# Tesseract.net
KiCad netlist of a schematic drawn in EAGLE
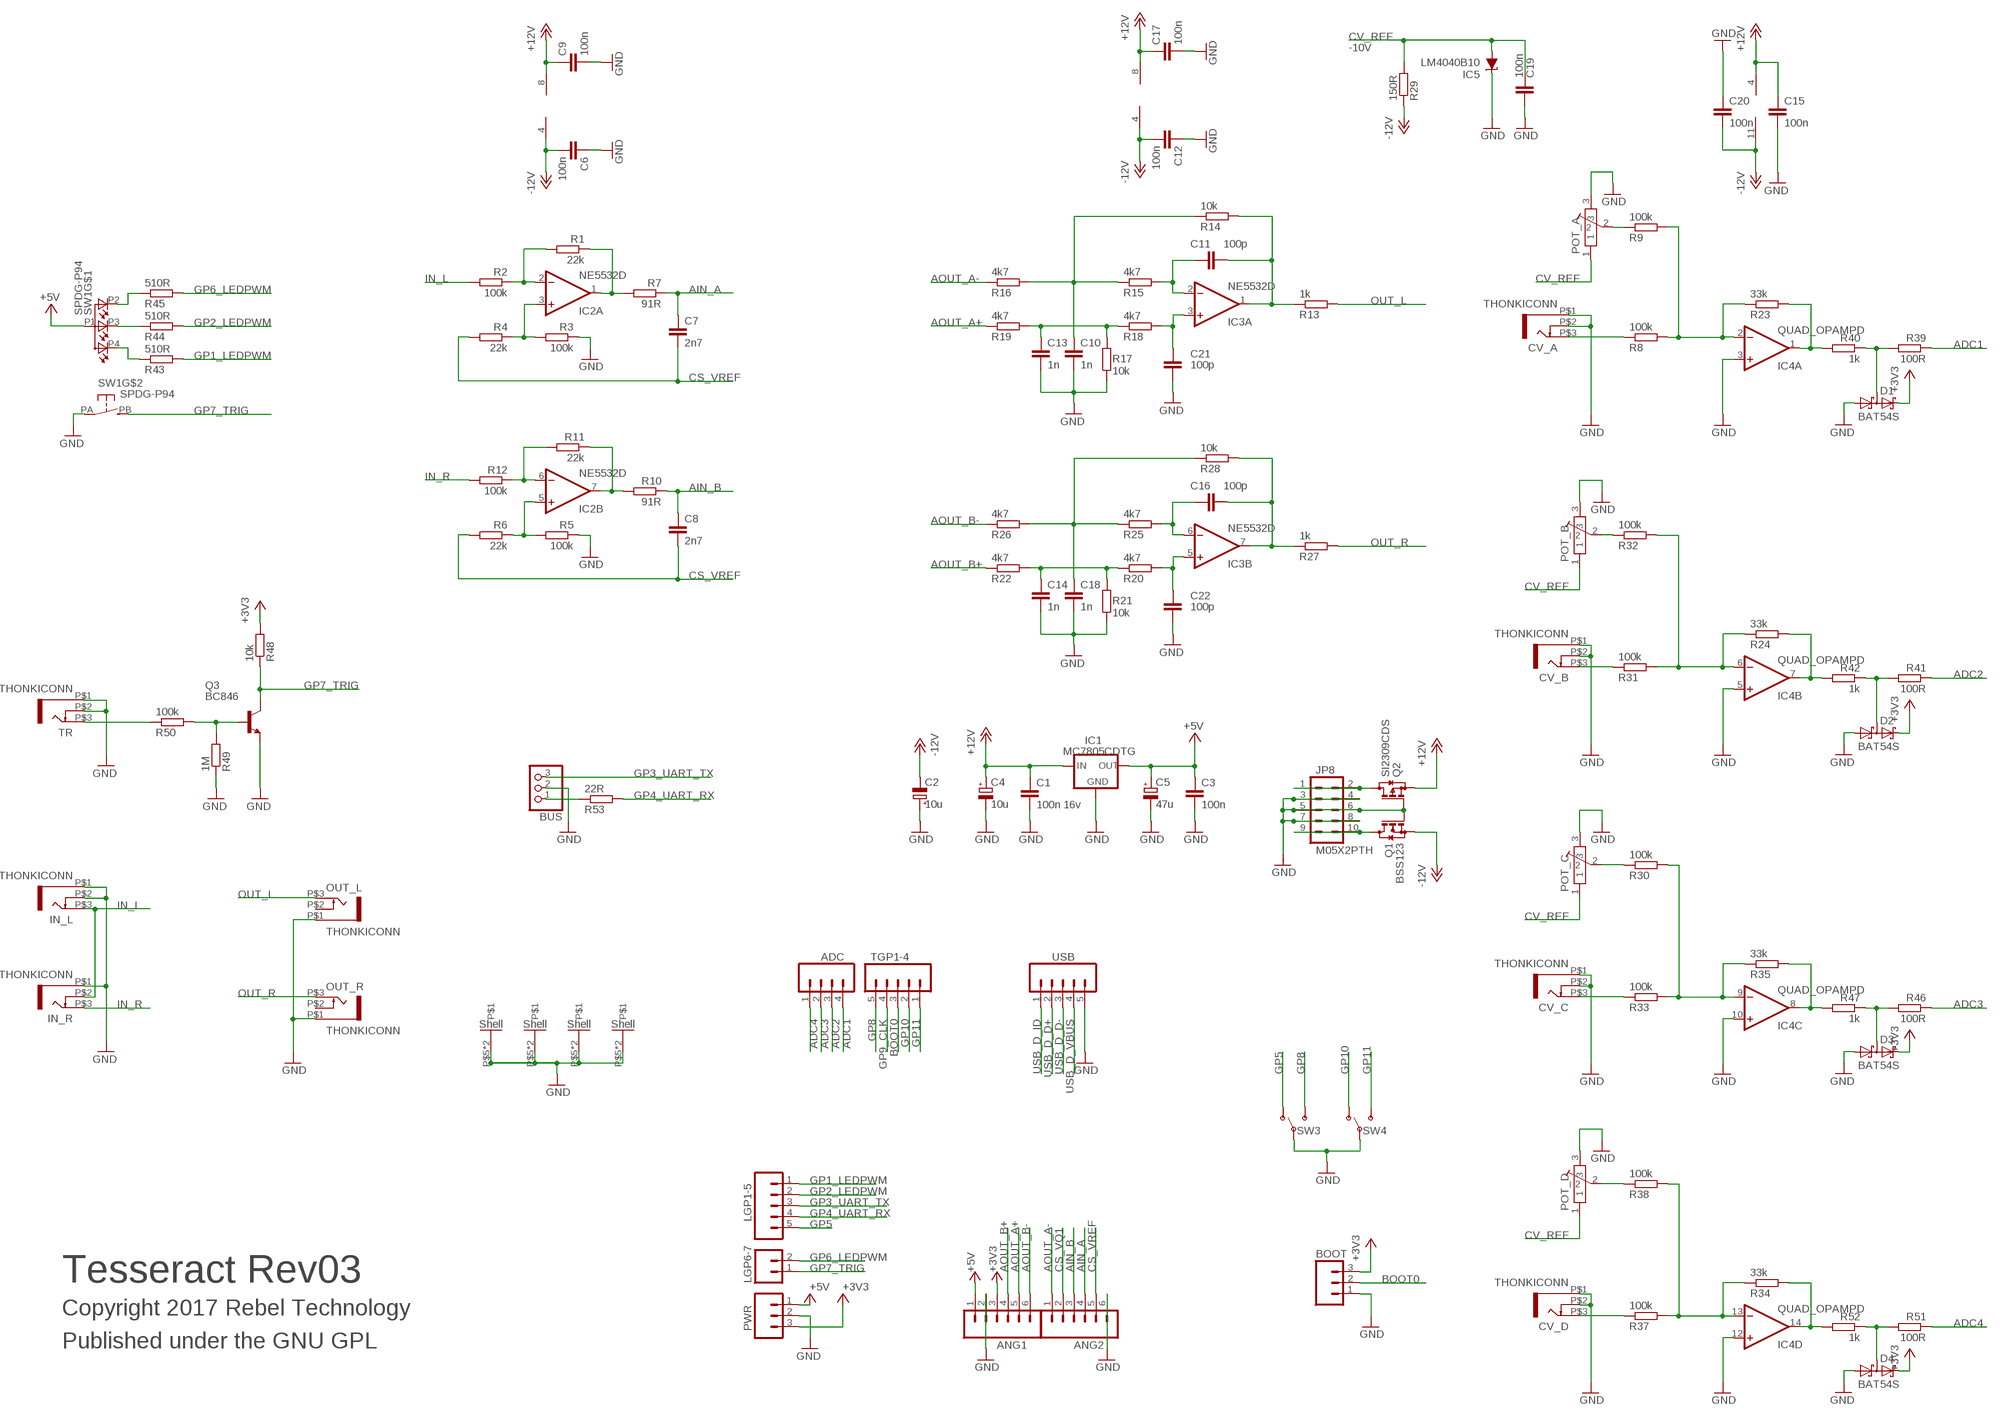
[diagram p0: schematic, sheet 1]

(export (version "E")
  (design (tool "Eeschema 10.0.6"))
  (components
    (comp (ref "ADC")
      (value "M04PTH")
      (footprint "eagle-import:1X04")
      (libsource (lib "eagle-import") (part "M04PTH"))
    )
    (comp (ref "ANG1")
      (value "M06SIP")
      (footprint "eagle-import:1X06")
      (libsource (lib "eagle-import") (part "M06SIP"))
    )
    (comp (ref "ANG2")
      (value "M06SIP")
      (footprint "eagle-import:1X06")
      (libsource (lib "eagle-import") (part "M06SIP"))
    )
    (comp (ref "BOOT")
      (value "M03PTH")
      (footprint "eagle-import:1X03")
      (libsource (lib "eagle-import") (part "M03PTH"))
    )
    (comp (ref "BUS")
      (value "CON-JST-1X03PH-TH")
      (footprint "eagle-import:JST-B3B-PH-KL")
      (libsource (lib "eagle-import") (part "CON-JST-1X03PH-TH"))
    )
    (comp (ref "C1")
      (value "100n 16v")
      (footprint "eagle-import:C0603")
      (libsource (lib "eagle-import") (part "C-EUC0603"))
    )
    (comp (ref "C2")
      (value "10u")
      (footprint "eagle-import:CPOL-5")
      (libsource (lib "eagle-import") (part "CPOL-EU153CLV-0505"))
    )
    (comp (ref "C3")
      (value "100n")
      (footprint "eagle-import:C0603")
      (libsource (lib "eagle-import") (part "C-EUC0603"))
    )
    (comp (ref "C4")
      (value "10u")
      (footprint "eagle-import:CPOL-5")
      (libsource (lib "eagle-import") (part "CPOL-EU153CLV-0505"))
    )
    (comp (ref "C5")
      (value "47u")
      (footprint "eagle-import:PANASONIC_C")
      (libsource (lib "eagle-import") (part "rcl_CPOL-EUC"))
    )
    (comp (ref "C6")
      (value "100n")
      (footprint "eagle-import:C0603")
      (libsource (lib "eagle-import") (part "resistor_C-EUC0603"))
    )
    (comp (ref "C7")
      (value "2n7")
      (footprint "eagle-import:C0603")
      (libsource (lib "eagle-import") (part "resistor_C-EUC0603"))
    )
    (comp (ref "C8")
      (value "2n7")
      (footprint "eagle-import:C0603")
      (libsource (lib "eagle-import") (part "resistor_C-EUC0603"))
    )
    (comp (ref "C9")
      (value "100n")
      (footprint "eagle-import:C0603")
      (libsource (lib "eagle-import") (part "resistor_C-EUC0603"))
    )
    (comp (ref "C10")
      (value "1n")
      (footprint "eagle-import:C0603")
      (libsource (lib "eagle-import") (part "resistor_C-EUC0603"))
    )
    (comp (ref "C11")
      (value "100p")
      (footprint "eagle-import:C0603")
      (libsource (lib "eagle-import") (part "resistor_C-EUC0603"))
    )
    (comp (ref "C12")
      (value "100n")
      (footprint "eagle-import:C0603")
      (libsource (lib "eagle-import") (part "resistor_C-EUC0603"))
    )
    (comp (ref "C13")
      (value "1n")
      (footprint "eagle-import:C0603")
      (libsource (lib "eagle-import") (part "resistor_C-EUC0603"))
    )
    (comp (ref "C14")
      (value "1n")
      (footprint "eagle-import:C0603")
      (libsource (lib "eagle-import") (part "resistor_C-EUC0603"))
    )
    (comp (ref "C15")
      (value "100n")
      (footprint "eagle-import:C0603")
      (libsource (lib "eagle-import") (part "resistor_C-EUC0603"))
    )
    (comp (ref "C16")
      (value "100p")
      (footprint "eagle-import:C0603")
      (libsource (lib "eagle-import") (part "resistor_C-EUC0603"))
    )
    (comp (ref "C17")
      (value "100n")
      (footprint "eagle-import:C0603")
      (libsource (lib "eagle-import") (part "resistor_C-EUC0603"))
    )
    (comp (ref "C18")
      (value "1n")
      (footprint "eagle-import:C0603")
      (libsource (lib "eagle-import") (part "resistor_C-EUC0603"))
    )
    (comp (ref "C19")
      (value "100n")
      (footprint "eagle-import:C0603")
      (libsource (lib "eagle-import") (part "resistor_C-EUC0603"))
    )
    (comp (ref "C20")
      (value "100n")
      (footprint "eagle-import:C0603")
      (libsource (lib "eagle-import") (part "resistor_C-EUC0603"))
    )
    (comp (ref "C21")
      (value "100p")
      (footprint "eagle-import:C0603")
      (libsource (lib "eagle-import") (part "resistor_C-EUC0603"))
    )
    (comp (ref "C22")
      (value "100p")
      (footprint "eagle-import:C0603")
      (libsource (lib "eagle-import") (part "resistor_C-EUC0603"))
    )
    (comp (ref "CV_A")
      (value "THONKICONN")
      (footprint "eagle-import:THONKICONN")
      (libsource (lib "eagle-import") (part "THONKICONN"))
    )
    (comp (ref "CV_B")
      (value "THONKICONN")
      (footprint "eagle-import:THONKICONN")
      (libsource (lib "eagle-import") (part "THONKICONN"))
    )
    (comp (ref "CV_C")
      (value "THONKICONN")
      (footprint "eagle-import:THONKICONN")
      (libsource (lib "eagle-import") (part "THONKICONN"))
    )
    (comp (ref "CV_D")
      (value "THONKICONN")
      (footprint "eagle-import:THONKICONN")
      (libsource (lib "eagle-import") (part "THONKICONN"))
    )
    (comp (ref "D1")
      (value "BAT54S")
      (footprint "eagle-import:SOT23")
      (libsource (lib "eagle-import") (part "BAT54S"))
    )
    (comp (ref "D2")
      (value "BAT54S")
      (footprint "eagle-import:SOT23")
      (libsource (lib "eagle-import") (part "BAT54S"))
    )
    (comp (ref "D3")
      (value "BAT54S")
      (footprint "eagle-import:SOT23")
      (libsource (lib "eagle-import") (part "BAT54S"))
    )
    (comp (ref "D4")
      (value "BAT54S")
      (footprint "eagle-import:SOT23")
      (libsource (lib "eagle-import") (part "BAT54S"))
    )
    (comp (ref "IC1")
      (value "MC7805CDTG")
      (footprint "eagle-import:DPACK")
      (libsource (lib "eagle-import") (part "MC78XX"))
    )
    (comp (ref "IC2")
      (value "NE5532D")
      (footprint "eagle-import:SO08")
      (libsource (lib "eagle-import") (part "NE5532D"))
    )
    (comp (ref "IC3")
      (value "NE5532D")
      (footprint "eagle-import:SO08")
      (libsource (lib "eagle-import") (part "NE5532D"))
    )
    (comp (ref "IC4")
      (value "QUAD_OPAMPD")
      (footprint "eagle-import:SO14")
      (libsource (lib "eagle-import") (part "QUAD_OPAMPD"))
    )
    (comp (ref "IC5")
      (value "LM4040B10")
      (footprint "eagle-import:DBZ_R-PDSO-G3")
      (fields (field (name "MF") "TEXAS INSTRUMENT CONNECTORS") (field (name "MPN") "LM4041C12QDBZT"))
      (libsource (lib "eagle-import") (part "LM4041DBZC12"))
    )
    (comp (ref "IN_L")
      (value "THONKICONN")
      (footprint "eagle-import:THONKICONN")
      (libsource (lib "eagle-import") (part "THONKICONN"))
    )
    (comp (ref "IN_R")
      (value "THONKICONN")
      (footprint "eagle-import:THONKICONN")
      (libsource (lib "eagle-import") (part "THONKICONN"))
    )
    (comp (ref "JP8")
      (value "M05X2PTH")
      (footprint "eagle-import:AVR_ICSP")
      (libsource (lib "eagle-import") (part "M05X2PTH"))
    )
    (comp (ref "LGP1-5")
      (value "M05PTH")
      (footprint "eagle-import:1X05")
      (libsource (lib "eagle-import") (part "M05PTH"))
    )
    (comp (ref "LGP6-7")
      (value "M02PTH")
      (footprint "eagle-import:1X02")
      (libsource (lib "eagle-import") (part "M02PTH"))
    )
    (comp (ref "OUT_L")
      (value "THONKICONN")
      (footprint "eagle-import:THONKICONN")
      (libsource (lib "eagle-import") (part "THONKICONN"))
    )
    (comp (ref "OUT_R")
      (value "THONKICONN")
      (footprint "eagle-import:THONKICONN")
      (libsource (lib "eagle-import") (part "THONKICONN"))
    )
    (comp (ref "POT_A")
      (value "POT-ALPS-RK09L1140")
      (footprint "eagle-import:POT-ALPS-RK09L1140")
      (libsource (lib "eagle-import") (part "POT-ALPS-RK09L1140"))
    )
    (comp (ref "POT_B")
      (value "POT-ALPS-RK09L1140")
      (footprint "eagle-import:POT-ALPS-RK09L1140")
      (libsource (lib "eagle-import") (part "POT-ALPS-RK09L1140"))
    )
    (comp (ref "POT_C")
      (value "POT-ALPS-RK09L1140")
      (footprint "eagle-import:POT-ALPS-RK09L1140")
      (libsource (lib "eagle-import") (part "POT-ALPS-RK09L1140"))
    )
    (comp (ref "POT_D")
      (value "POT-ALPS-RK09L1140")
      (footprint "eagle-import:POT-ALPS-RK09L1140")
      (libsource (lib "eagle-import") (part "POT-ALPS-RK09L1140"))
    )
    (comp (ref "PWR")
      (value "M03PTH")
      (footprint "eagle-import:1X03")
      (libsource (lib "eagle-import") (part "M03PTH"))
    )
    (comp (ref "Q1")
      (value "BSS123")
      (footprint "eagle-import:SOT23")
      (libsource (lib "eagle-import") (part "BSS123"))
    )
    (comp (ref "Q2")
      (value "SI2309CDS")
      (footprint "eagle-import:SOT23")
      (libsource (lib "eagle-import") (part "BSS84"))
    )
    (comp (ref "Q3")
      (value "BC846")
      (footprint "eagle-import:SOT23")
      (libsource (lib "eagle-import") (part "BC846"))
    )
    (comp (ref "R1")
      (value "22k")
      (footprint "eagle-import:0603")
      (libsource (lib "eagle-import") (part "R-EU_0603"))
    )
    (comp (ref "R2")
      (value "100k")
      (footprint "eagle-import:0603")
      (libsource (lib "eagle-import") (part "R-EU_0603"))
    )
    (comp (ref "R3")
      (value "100k")
      (footprint "eagle-import:0603")
      (libsource (lib "eagle-import") (part "R-EU_0603"))
    )
    (comp (ref "R4")
      (value "22k")
      (footprint "eagle-import:0603")
      (libsource (lib "eagle-import") (part "R-EU_0603"))
    )
    (comp (ref "R5")
      (value "100k")
      (footprint "eagle-import:0603")
      (libsource (lib "eagle-import") (part "R-EU_0603"))
    )
    (comp (ref "R6")
      (value "22k")
      (footprint "eagle-import:0603")
      (libsource (lib "eagle-import") (part "R-EU_0603"))
    )
    (comp (ref "R7")
      (value "91R")
      (footprint "eagle-import:0603")
      (libsource (lib "eagle-import") (part "R-EU_0603"))
    )
    (comp (ref "R8")
      (value "100k")
      (footprint "eagle-import:0603")
      (libsource (lib "eagle-import") (part "R-EU_0603"))
    )
    (comp (ref "R9")
      (value "100k")
      (footprint "eagle-import:0603")
      (libsource (lib "eagle-import") (part "R-EU_0603"))
    )
    (comp (ref "R10")
      (value "91R")
      (footprint "eagle-import:0603")
      (libsource (lib "eagle-import") (part "R-EU_0603"))
    )
    (comp (ref "R11")
      (value "22k")
      (footprint "eagle-import:0603")
      (libsource (lib "eagle-import") (part "R-EU_0603"))
    )
    (comp (ref "R12")
      (value "100k")
      (footprint "eagle-import:0603")
      (libsource (lib "eagle-import") (part "R-EU_0603"))
    )
    (comp (ref "R13")
      (value "1k")
      (footprint "eagle-import:0603")
      (libsource (lib "eagle-import") (part "R-EU_0603"))
    )
    (comp (ref "R14")
      (value "10k")
      (footprint "eagle-import:0603")
      (libsource (lib "eagle-import") (part "R-EU_0603"))
    )
    (comp (ref "R15")
      (value "4k7")
      (footprint "eagle-import:0603")
      (libsource (lib "eagle-import") (part "R-EU_0603"))
    )
    (comp (ref "R16")
      (value "4k7")
      (footprint "eagle-import:0603")
      (libsource (lib "eagle-import") (part "R-EU_0603"))
    )
    (comp (ref "R17")
      (value "10k")
      (footprint "eagle-import:0603")
      (libsource (lib "eagle-import") (part "R-EU_0603"))
    )
    (comp (ref "R18")
      (value "4k7")
      (footprint "eagle-import:0603")
      (libsource (lib "eagle-import") (part "R-EU_0603"))
    )
    (comp (ref "R19")
      (value "4k7")
      (footprint "eagle-import:0603")
      (libsource (lib "eagle-import") (part "R-EU_0603"))
    )
    (comp (ref "R20")
      (value "4k7")
      (footprint "eagle-import:0603")
      (libsource (lib "eagle-import") (part "R-EU_0603"))
    )
    (comp (ref "R21")
      (value "10k")
      (footprint "eagle-import:0603")
      (libsource (lib "eagle-import") (part "R-EU_0603"))
    )
    (comp (ref "R22")
      (value "4k7")
      (footprint "eagle-import:0603")
      (libsource (lib "eagle-import") (part "R-EU_0603"))
    )
    (comp (ref "R23")
      (value "33k")
      (footprint "eagle-import:0603")
      (libsource (lib "eagle-import") (part "R-EU_0603"))
    )
    (comp (ref "R24")
      (value "33k")
      (footprint "eagle-import:0603")
      (libsource (lib "eagle-import") (part "R-EU_0603"))
    )
    (comp (ref "R25")
      (value "4k7")
      (footprint "eagle-import:0603")
      (libsource (lib "eagle-import") (part "R-EU_0603"))
    )
    (comp (ref "R26")
      (value "4k7")
      (footprint "eagle-import:0603")
      (libsource (lib "eagle-import") (part "R-EU_0603"))
    )
    (comp (ref "R27")
      (value "1k")
      (footprint "eagle-import:0603")
      (libsource (lib "eagle-import") (part "R-EU_0603"))
    )
    (comp (ref "R28")
      (value "10k")
      (footprint "eagle-import:0603")
      (libsource (lib "eagle-import") (part "R-EU_0603"))
    )
    (comp (ref "R29")
      (value "150R")
      (footprint "eagle-import:0603")
      (libsource (lib "eagle-import") (part "R-EU_0603"))
    )
    (comp (ref "R30")
      (value "100k")
      (footprint "eagle-import:0603")
      (libsource (lib "eagle-import") (part "R-EU_0603"))
    )
    (comp (ref "R31")
      (value "100k")
      (footprint "eagle-import:0603")
      (libsource (lib "eagle-import") (part "R-EU_0603"))
    )
    (comp (ref "R32")
      (value "100k")
      (footprint "eagle-import:0603")
      (libsource (lib "eagle-import") (part "R-EU_0603"))
    )
    (comp (ref "R33")
      (value "100k")
      (footprint "eagle-import:0603")
      (libsource (lib "eagle-import") (part "R-EU_0603"))
    )
    (comp (ref "R34")
      (value "33k")
      (footprint "eagle-import:0603")
      (libsource (lib "eagle-import") (part "R-EU_0603"))
    )
    (comp (ref "R35")
      (value "33k")
      (footprint "eagle-import:0603")
      (libsource (lib "eagle-import") (part "R-EU_0603"))
    )
    (comp (ref "R37")
      (value "100k")
      (footprint "eagle-import:0603")
      (libsource (lib "eagle-import") (part "R-EU_0603"))
    )
    (comp (ref "R38")
      (value "100k")
      (footprint "eagle-import:0603")
      (libsource (lib "eagle-import") (part "R-EU_0603"))
    )
    (comp (ref "R39")
      (value "100R")
      (footprint "eagle-import:0603")
      (libsource (lib "eagle-import") (part "R-EU_0603"))
    )
    (comp (ref "R40")
      (value "1k")
      (footprint "eagle-import:0603")
      (libsource (lib "eagle-import") (part "R-EU_0603"))
    )
    (comp (ref "R41")
      (value "100R")
      (footprint "eagle-import:0603")
      (libsource (lib "eagle-import") (part "R-EU_0603"))
    )
    (comp (ref "R42")
      (value "1k")
      (footprint "eagle-import:0603")
      (libsource (lib "eagle-import") (part "R-EU_0603"))
    )
    (comp (ref "R43")
      (value "510R")
      (footprint "eagle-import:0603")
      (libsource (lib "eagle-import") (part "R-EU_0603"))
    )
    (comp (ref "R44")
      (value "510R")
      (footprint "eagle-import:0603")
      (libsource (lib "eagle-import") (part "R-EU_0603"))
    )
    (comp (ref "R45")
      (value "510R")
      (footprint "eagle-import:0603")
      (libsource (lib "eagle-import") (part "R-EU_0603"))
    )
    (comp (ref "R46")
      (value "100R")
      (footprint "eagle-import:0603")
      (libsource (lib "eagle-import") (part "R-EU_0603"))
    )
    (comp (ref "R47")
      (value "1k")
      (footprint "eagle-import:0603")
      (libsource (lib "eagle-import") (part "R-EU_0603"))
    )
    (comp (ref "R48")
      (value "10k")
      (footprint "eagle-import:0603")
      (libsource (lib "eagle-import") (part "R-EU_0603"))
    )
    (comp (ref "R49")
      (value "1M")
      (footprint "eagle-import:0603")
      (libsource (lib "eagle-import") (part "R-EU_0603"))
    )
    (comp (ref "R50")
      (value "100k")
      (footprint "eagle-import:0603")
      (libsource (lib "eagle-import") (part "R-EU_0603"))
    )
    (comp (ref "R51")
      (value "100R")
      (footprint "eagle-import:0603")
      (libsource (lib "eagle-import") (part "R-EU_0603"))
    )
    (comp (ref "R52")
      (value "1k")
      (footprint "eagle-import:0603")
      (libsource (lib "eagle-import") (part "R-EU_0603"))
    )
    (comp (ref "R53")
      (value "22R")
      (footprint "eagle-import:0603")
      (libsource (lib "eagle-import") (part "R-EU_0603"))
    )
    (comp (ref "SW1")
      (value "SPDG-P94")
      (footprint "eagle-import:SPDG-P94")
      (libsource (lib "eagle-import") (part "SPDG-P94"))
    )
    (comp (ref "SW3")
      (value "SUB-MIN-SPDT")
      (footprint "eagle-import:SUB-MIN-SPDT")
      (libsource (lib "eagle-import") (part "SUB-MIN-SPDT"))
    )
    (comp (ref "SW4")
      (value "SUB-MIN-SPDT")
      (footprint "eagle-import:SUB-MIN-SPDT")
      (libsource (lib "eagle-import") (part "SUB-MIN-SPDT"))
    )
    (comp (ref "TGP1-4")
      (value "M05PTH")
      (footprint "eagle-import:1X05")
      (libsource (lib "eagle-import") (part "M05PTH"))
    )
    (comp (ref "TR")
      (value "THONKICONN")
      (footprint "eagle-import:THONKICONN")
      (libsource (lib "eagle-import") (part "THONKICONN"))
    )
    (comp (ref "USB")
      (value "M05PTH")
      (footprint "eagle-import:1X05")
      (libsource (lib "eagle-import") (part "M05PTH"))
    )
  )
  (nets
    (net (code "1") (name "+3V3") (class "Default")
      (node (ref "ANG1") (pin "3") (pinfunction "3_3") (pintype "passive"))
      (node (ref "BOOT") (pin "3") (pinfunction "3_3") (pintype "passive"))
      (node (ref "D1") (pin "2") (pinfunction "C2_2") (pintype "passive"))
      (node (ref "D2") (pin "2") (pinfunction "C2_2") (pintype "passive"))
      (node (ref "D3") (pin "2") (pinfunction "C2_2") (pintype "passive"))
      (node (ref "D4") (pin "2") (pinfunction "C2_2") (pintype "passive"))
      (node (ref "PWR") (pin "3") (pinfunction "3_3") (pintype "passive"))
      (node (ref "R48") (pin "2") (pinfunction "2_2") (pintype "passive"))
    )
    (net (code "2") (name "+5V") (class "Default")
      (node (ref "ANG1") (pin "1") (pinfunction "1_1") (pintype "passive"))
      (node (ref "C3") (pin "1") (pinfunction "1_1") (pintype "passive"))
      (node (ref "C5") (pin "+") (pinfunction "+_+") (pintype "passive"))
      (node (ref "IC1") (pin "3") (pinfunction "OUT_3") (pintype "passive"))
      (node (ref "PWR") (pin "1") (pinfunction "1_1") (pintype "passive"))
      (node (ref "SW1") (pin "P1") (pinfunction "A_P1") (pintype "passive"))
    )
    (net (code "3") (name "+12V") (class "Default")
      (node (ref "C1") (pin "1") (pinfunction "1_1") (pintype "passive"))
      (node (ref "C15") (pin "1") (pinfunction "1_1") (pintype "passive"))
      (node (ref "C17") (pin "1") (pinfunction "1_1") (pintype "passive"))
      (node (ref "C4") (pin "+") (pinfunction "+_+") (pintype "passive"))
      (node (ref "C9") (pin "1") (pinfunction "1_1") (pintype "passive"))
      (node (ref "IC1") (pin "1") (pinfunction "IN_1") (pintype "input"))
      (node (ref "IC2") (pin "8") (pinfunction "V+_8") (pintype "power_in"))
      (node (ref "IC3") (pin "8") (pinfunction "V+_8") (pintype "power_in"))
      (node (ref "IC4") (pin "4") (pinfunction "V+_4") (pintype "power_in"))
      (node (ref "Q2") (pin "2") (pinfunction "S_2") (pintype "passive"))
    )
    (net (code "4") (name "-12V") (class "Default")
      (node (ref "C12") (pin "2") (pinfunction "2_2") (pintype "passive"))
      (node (ref "C2") (pin "-") (pinfunction "-_-") (pintype "passive"))
      (node (ref "C20") (pin "2") (pinfunction "2_2") (pintype "passive"))
      (node (ref "C6") (pin "2") (pinfunction "2_2") (pintype "passive"))
      (node (ref "IC2") (pin "4") (pinfunction "V-_4") (pintype "power_in"))
      (node (ref "IC3") (pin "4") (pinfunction "V-_4") (pintype "power_in"))
      (node (ref "IC4") (pin "11") (pinfunction "V-_11") (pintype "power_in"))
      (node (ref "Q1") (pin "2") (pinfunction "S_2") (pintype "passive"))
      (node (ref "R29") (pin "1") (pinfunction "1_1") (pintype "passive"))
    )
    (net (code "5") (name "/ADC1") (class "Default")
      (node (ref "ADC") (pin "4") (pinfunction "4_4") (pintype "passive"))
      (node (ref "R39") (pin "1") (pinfunction "1_1") (pintype "passive"))
    )
    (net (code "6") (name "/ADC2") (class "Default")
      (node (ref "ADC") (pin "3") (pinfunction "3_3") (pintype "passive"))
      (node (ref "R41") (pin "1") (pinfunction "1_1") (pintype "passive"))
    )
    (net (code "7") (name "/ADC3") (class "Default")
      (node (ref "ADC") (pin "2") (pinfunction "2_2") (pintype "passive"))
      (node (ref "R46") (pin "1") (pinfunction "1_1") (pintype "passive"))
    )
    (net (code "8") (name "/ADC4") (class "Default")
      (node (ref "ADC") (pin "1") (pinfunction "1_1") (pintype "passive"))
      (node (ref "R51") (pin "1") (pinfunction "1_1") (pintype "passive"))
    )
    (net (code "9") (name "/AIN_A") (class "Default")
      (node (ref "ANG2") (pin "4") (pinfunction "4_4") (pintype "passive"))
      (node (ref "C7") (pin "1") (pinfunction "1_1") (pintype "passive"))
      (node (ref "R7") (pin "1") (pinfunction "1_1") (pintype "passive"))
    )
    (net (code "10") (name "/AIN_B") (class "Default")
      (node (ref "ANG2") (pin "3") (pinfunction "3_3") (pintype "passive"))
      (node (ref "C8") (pin "1") (pinfunction "1_1") (pintype "passive"))
      (node (ref "R10") (pin "1") (pinfunction "1_1") (pintype "passive"))
    )
    (net (code "11") (name "/AOUT_A+") (class "Default")
      (node (ref "ANG1") (pin "5") (pinfunction "5_5") (pintype "passive"))
      (node (ref "R19") (pin "1") (pinfunction "1_1") (pintype "passive"))
    )
    (net (code "12") (name "/AOUT_A-") (class "Default")
      (node (ref "ANG2") (pin "1") (pinfunction "1_1") (pintype "passive"))
      (node (ref "R16") (pin "1") (pinfunction "1_1") (pintype "passive"))
    )
    (net (code "13") (name "/AOUT_B+") (class "Default")
      (node (ref "ANG1") (pin "4") (pinfunction "4_4") (pintype "passive"))
      (node (ref "R22") (pin "1") (pinfunction "1_1") (pintype "passive"))
    )
    (net (code "14") (name "/AOUT_B-") (class "Default")
      (node (ref "ANG1") (pin "6") (pinfunction "6_6") (pintype "passive"))
      (node (ref "R26") (pin "1") (pinfunction "1_1") (pintype "passive"))
    )
    (net (code "15") (name "/BOOT0") (class "Default")
      (node (ref "BOOT") (pin "2") (pinfunction "2_2") (pintype "passive"))
      (node (ref "TGP1-4") (pin "3") (pinfunction "3_3") (pintype "passive"))
    )
    (net (code "16") (name "/CS_VQ1") (class "Default")
      (node (ref "ANG2") (pin "2") (pinfunction "2_2") (pintype "passive"))
    )
    (net (code "17") (name "/CS_VREF") (class "Default")
      (node (ref "ANG2") (pin "5") (pinfunction "5_5") (pintype "passive"))
      (node (ref "C7") (pin "2") (pinfunction "2_2") (pintype "passive"))
      (node (ref "C8") (pin "2") (pinfunction "2_2") (pintype "passive"))
      (node (ref "R4") (pin "2") (pinfunction "2_2") (pintype "passive"))
      (node (ref "R6") (pin "2") (pinfunction "2_2") (pintype "passive"))
    )
    (net (code "18") (name "/CV_REF") (class "Default")
      (node (ref "C19") (pin "1") (pinfunction "1_1") (pintype "passive"))
      (node (ref "IC5") (pin "2") (pinfunction "A_2") (pintype "passive"))
      (node (ref "POT_A") (pin "1") (pinfunction "1_1") (pintype "bidirectional"))
      (node (ref "POT_B") (pin "1") (pinfunction "1_1") (pintype "bidirectional"))
      (node (ref "POT_C") (pin "1") (pinfunction "1_1") (pintype "bidirectional"))
      (node (ref "POT_D") (pin "1") (pinfunction "1_1") (pintype "bidirectional"))
      (node (ref "R29") (pin "2") (pinfunction "2_2") (pintype "passive"))
    )
    (net (code "19") (name "/GP1_LEDPWM") (class "Default")
      (node (ref "LGP1-5") (pin "1") (pinfunction "1_1") (pintype "passive"))
      (node (ref "R43") (pin "2") (pinfunction "2_2") (pintype "passive"))
    )
    (net (code "20") (name "/GP2_LEDPWM") (class "Default")
      (node (ref "LGP1-5") (pin "2") (pinfunction "2_2") (pintype "passive"))
      (node (ref "R44") (pin "2") (pinfunction "2_2") (pintype "passive"))
    )
    (net (code "21") (name "/GP3_UART_TX") (class "Default")
      (node (ref "BUS") (pin "3") (pinfunction "3_3") (pintype "passive"))
      (node (ref "LGP1-5") (pin "3") (pinfunction "3_3") (pintype "passive"))
    )
    (net (code "22") (name "/GP4_UART_RX") (class "Default")
      (node (ref "LGP1-5") (pin "4") (pinfunction "4_4") (pintype "passive"))
      (node (ref "R53") (pin "2") (pinfunction "2_2") (pintype "passive"))
    )
    (net (code "23") (name "/GP5") (class "Default")
      (node (ref "LGP1-5") (pin "5") (pinfunction "5_5") (pintype "passive"))
      (node (ref "SW3") (pin "1") (pinfunction "O_1") (pintype "passive"))
    )
    (net (code "24") (name "/GP6_LEDPWM") (class "Default")
      (node (ref "LGP6-7") (pin "2") (pinfunction "2_2") (pintype "passive"))
      (node (ref "R45") (pin "2") (pinfunction "2_2") (pintype "passive"))
    )
    (net (code "25") (name "/GP7_TRIG") (class "Default")
      (node (ref "LGP6-7") (pin "1") (pinfunction "1_1") (pintype "passive"))
      (node (ref "Q3") (pin "3") (pinfunction "C_3") (pintype "passive"))
      (node (ref "R48") (pin "1") (pinfunction "1_1") (pintype "passive"))
      (node (ref "SW1") (pin "PB") (pinfunction "S_PB") (pintype "passive"))
    )
    (net (code "26") (name "/GP8") (class "Default")
      (node (ref "SW3") (pin "3") (pinfunction "S_3") (pintype "passive"))
      (node (ref "TGP1-4") (pin "5") (pinfunction "5_5") (pintype "passive"))
    )
    (net (code "27") (name "/GP9_CLK") (class "Default")
      (node (ref "TGP1-4") (pin "4") (pinfunction "4_4") (pintype "passive"))
    )
    (net (code "28") (name "/GP10") (class "Default")
      (node (ref "SW4") (pin "1") (pinfunction "O_1") (pintype "passive"))
      (node (ref "TGP1-4") (pin "2") (pinfunction "2_2") (pintype "passive"))
    )
    (net (code "29") (name "/GP11") (class "Default")
      (node (ref "SW4") (pin "3") (pinfunction "S_3") (pintype "passive"))
      (node (ref "TGP1-4") (pin "1") (pinfunction "1_1") (pintype "passive"))
    )
    (net (code "30") (name "/IN_L") (class "Default")
      (node (ref "IN_L") (pin "P$3") (pinfunction "3_P$3") (pintype "passive"))
      (node (ref "IN_R") (pin "P$2") (pinfunction "4_P$2") (pintype "passive"))
      (node (ref "R2") (pin "2") (pinfunction "2_2") (pintype "passive"))
    )
    (net (code "31") (name "/IN_R") (class "Default")
      (node (ref "IN_R") (pin "P$3") (pinfunction "3_P$3") (pintype "passive"))
      (node (ref "R12") (pin "2") (pinfunction "2_2") (pintype "passive"))
    )
    (net (code "32") (name "/OUT_L") (class "Default")
      (node (ref "OUT_L") (pin "P$3") (pinfunction "3_P$3") (pintype "passive"))
      (node (ref "R13") (pin "2") (pinfunction "2_2") (pintype "passive"))
    )
    (net (code "33") (name "/OUT_R") (class "Default")
      (node (ref "OUT_R") (pin "P$3") (pinfunction "3_P$3") (pintype "passive"))
      (node (ref "R27") (pin "2") (pinfunction "2_2") (pintype "passive"))
    )
    (net (code "34") (name "/USB_D_D+") (class "Default")
      (node (ref "USB") (pin "2") (pinfunction "2_2") (pintype "passive"))
    )
    (net (code "35") (name "/USB_D_D-") (class "Default")
      (node (ref "USB") (pin "3") (pinfunction "3_3") (pintype "passive"))
    )
    (net (code "36") (name "/USB_D_ID") (class "Default")
      (node (ref "USB") (pin "1") (pinfunction "1_1") (pintype "passive"))
    )
    (net (code "37") (name "/USB_D_VBUS") (class "Default")
      (node (ref "USB") (pin "4") (pinfunction "4_4") (pintype "passive"))
    )
    (net (code "38") (name "GND") (class "Default")
      (node (ref "ANG1") (pin "2") (pinfunction "2_2") (pintype "passive"))
      (node (ref "ANG2") (pin "6") (pinfunction "6_6") (pintype "passive"))
      (node (ref "BOOT") (pin "1") (pinfunction "1_1") (pintype "passive"))
      (node (ref "BUS") (pin "2") (pinfunction "2_2") (pintype "passive"))
      (node (ref "C1") (pin "2") (pinfunction "2_2") (pintype "passive"))
      (node (ref "C10") (pin "2") (pinfunction "2_2") (pintype "passive"))
      (node (ref "C12") (pin "1") (pinfunction "1_1") (pintype "passive"))
      (node (ref "C13") (pin "2") (pinfunction "2_2") (pintype "passive"))
      (node (ref "C14") (pin "2") (pinfunction "2_2") (pintype "passive"))
      (node (ref "C15") (pin "2") (pinfunction "2_2") (pintype "passive"))
      (node (ref "C17") (pin "2") (pinfunction "2_2") (pintype "passive"))
      (node (ref "C18") (pin "2") (pinfunction "2_2") (pintype "passive"))
      (node (ref "C19") (pin "2") (pinfunction "2_2") (pintype "passive"))
      (node (ref "C2") (pin "+") (pinfunction "+_+") (pintype "passive"))
      (node (ref "C20") (pin "1") (pinfunction "1_1") (pintype "passive"))
      (node (ref "C21") (pin "2") (pinfunction "2_2") (pintype "passive"))
      (node (ref "C22") (pin "2") (pinfunction "2_2") (pintype "passive"))
      (node (ref "C3") (pin "2") (pinfunction "2_2") (pintype "passive"))
      (node (ref "C4") (pin "-") (pinfunction "-_-") (pintype "passive"))
      (node (ref "C5") (pin "-") (pinfunction "-_-") (pintype "passive"))
      (node (ref "C6") (pin "1") (pinfunction "1_1") (pintype "passive"))
      (node (ref "C9") (pin "2") (pinfunction "2_2") (pintype "passive"))
      (node (ref "CV_A") (pin "P$1") (pinfunction "5_P$1") (pintype "passive"))
      (node (ref "CV_A") (pin "P$2") (pinfunction "4_P$2") (pintype "passive"))
      (node (ref "CV_B") (pin "P$1") (pinfunction "5_P$1") (pintype "passive"))
      (node (ref "CV_B") (pin "P$2") (pinfunction "4_P$2") (pintype "passive"))
      (node (ref "CV_C") (pin "P$1") (pinfunction "5_P$1") (pintype "passive"))
      (node (ref "CV_C") (pin "P$2") (pinfunction "4_P$2") (pintype "passive"))
      (node (ref "CV_D") (pin "P$1") (pinfunction "5_P$1") (pintype "passive"))
      (node (ref "CV_D") (pin "P$2") (pinfunction "4_P$2") (pintype "passive"))
      (node (ref "D1") (pin "1") (pinfunction "A1_1") (pintype "passive"))
      (node (ref "D2") (pin "1") (pinfunction "A1_1") (pintype "passive"))
      (node (ref "D3") (pin "1") (pinfunction "A1_1") (pintype "passive"))
      (node (ref "D4") (pin "1") (pinfunction "A1_1") (pintype "passive"))
      (node (ref "IC1") (pin "4") (pinfunction "GND_4") (pintype "input"))
      (node (ref "IC4") (pin "10") (pinfunction "+IN_10") (pintype "input"))
      (node (ref "IC4") (pin "12") (pinfunction "+IN_12") (pintype "input"))
      (node (ref "IC4") (pin "3") (pinfunction "+IN_3") (pintype "input"))
      (node (ref "IC4") (pin "5") (pinfunction "+IN_5") (pintype "input"))
      (node (ref "IC5") (pin "1") (pinfunction "C_1") (pintype "passive"))
      (node (ref "IN_L") (pin "P$1") (pinfunction "5_P$1") (pintype "passive"))
      (node (ref "IN_L") (pin "P$2") (pinfunction "4_P$2") (pintype "passive"))
      (node (ref "IN_R") (pin "P$1") (pinfunction "5_P$1") (pintype "passive"))
      (node (ref "JP8") (pin "3") (pinfunction "3_3") (pintype "passive"))
      (node (ref "JP8") (pin "4") (pinfunction "4_4") (pintype "passive"))
      (node (ref "JP8") (pin "5") (pinfunction "5_5") (pintype "passive"))
      (node (ref "JP8") (pin "6") (pinfunction "6_6") (pintype "passive"))
      (node (ref "JP8") (pin "7") (pinfunction "7_7") (pintype "passive"))
      (node (ref "JP8") (pin "8") (pinfunction "8_8") (pintype "passive"))
      (node (ref "OUT_L") (pin "P$1") (pinfunction "5_P$1") (pintype "passive"))
      (node (ref "OUT_R") (pin "P$1") (pinfunction "5_P$1") (pintype "passive"))
      (node (ref "POT_A") (pin "3") (pinfunction "3_3") (pintype "bidirectional"))
      (node (ref "POT_A") (pin "P$5") (pinfunction "P$1_P$5") (pintype "bidirectional"))
      (node (ref "POT_A") (pin "P$6") (pinfunction "P$1_P$6") (pintype "bidirectional"))
      (node (ref "POT_B") (pin "3") (pinfunction "3_3") (pintype "bidirectional"))
      (node (ref "POT_B") (pin "P$5") (pinfunction "P$1_P$5") (pintype "bidirectional"))
      (node (ref "POT_B") (pin "P$6") (pinfunction "P$1_P$6") (pintype "bidirectional"))
      (node (ref "POT_C") (pin "3") (pinfunction "3_3") (pintype "bidirectional"))
      (node (ref "POT_C") (pin "P$5") (pinfunction "P$1_P$5") (pintype "bidirectional"))
      (node (ref "POT_C") (pin "P$6") (pinfunction "P$1_P$6") (pintype "bidirectional"))
      (node (ref "POT_D") (pin "3") (pinfunction "3_3") (pintype "bidirectional"))
      (node (ref "POT_D") (pin "P$5") (pinfunction "P$1_P$5") (pintype "bidirectional"))
      (node (ref "POT_D") (pin "P$6") (pinfunction "P$1_P$6") (pintype "bidirectional"))
      (node (ref "PWR") (pin "2") (pinfunction "2_2") (pintype "passive"))
      (node (ref "Q1") (pin "1") (pinfunction "G_1") (pintype "passive"))
      (node (ref "Q2") (pin "1") (pinfunction "G_1") (pintype "passive"))
      (node (ref "Q3") (pin "2") (pinfunction "E_2") (pintype "passive"))
      (node (ref "R17") (pin "1") (pinfunction "1_1") (pintype "passive"))
      (node (ref "R21") (pin "1") (pinfunction "1_1") (pintype "passive"))
      (node (ref "R3") (pin "1") (pinfunction "1_1") (pintype "passive"))
      (node (ref "R49") (pin "1") (pinfunction "1_1") (pintype "passive"))
      (node (ref "R5") (pin "1") (pinfunction "1_1") (pintype "passive"))
      (node (ref "SW1") (pin "PA") (pinfunction "P_PA") (pintype "passive"))
      (node (ref "SW3") (pin "2") (pinfunction "P_2") (pintype "passive"))
      (node (ref "SW4") (pin "2") (pinfunction "P_2") (pintype "passive"))
      (node (ref "TR") (pin "P$1") (pinfunction "5_P$1") (pintype "passive"))
      (node (ref "TR") (pin "P$2") (pinfunction "4_P$2") (pintype "passive"))
      (node (ref "USB") (pin "5") (pinfunction "5_5") (pintype "passive"))
    )
    (net (code "39") (name "Net-(BUS-Pad1)") (class "Default")
      (node (ref "BUS") (pin "1") (pinfunction "1_1") (pintype "passive"))
      (node (ref "R53") (pin "1") (pinfunction "1_1") (pintype "passive"))
    )
    (net (code "40") (name "Net-(C10-Pad1)") (class "Default")
      (node (ref "C10") (pin "1") (pinfunction "1_1") (pintype "passive"))
      (node (ref "R14") (pin "1") (pinfunction "1_1") (pintype "passive"))
      (node (ref "R15") (pin "1") (pinfunction "1_1") (pintype "passive"))
      (node (ref "R16") (pin "2") (pinfunction "2_2") (pintype "passive"))
    )
    (net (code "41") (name "Net-(C13-Pad1)") (class "Default")
      (node (ref "C13") (pin "1") (pinfunction "1_1") (pintype "passive"))
      (node (ref "R17") (pin "2") (pinfunction "2_2") (pintype "passive"))
      (node (ref "R18") (pin "1") (pinfunction "1_1") (pintype "passive"))
      (node (ref "R19") (pin "2") (pinfunction "2_2") (pintype "passive"))
    )
    (net (code "42") (name "Net-(C14-Pad1)") (class "Default")
      (node (ref "C14") (pin "1") (pinfunction "1_1") (pintype "passive"))
      (node (ref "R20") (pin "1") (pinfunction "1_1") (pintype "passive"))
      (node (ref "R21") (pin "2") (pinfunction "2_2") (pintype "passive"))
      (node (ref "R22") (pin "2") (pinfunction "2_2") (pintype "passive"))
    )
    (net (code "43") (name "Net-(C18-Pad1)") (class "Default")
      (node (ref "C18") (pin "1") (pinfunction "1_1") (pintype "passive"))
      (node (ref "R25") (pin "1") (pinfunction "1_1") (pintype "passive"))
      (node (ref "R26") (pin "2") (pinfunction "2_2") (pintype "passive"))
      (node (ref "R28") (pin "1") (pinfunction "1_1") (pintype "passive"))
    )
    (net (code "44") (name "Net-(CV_A-3)") (class "Default")
      (node (ref "CV_A") (pin "P$3") (pinfunction "3_P$3") (pintype "passive"))
      (node (ref "R8") (pin "1") (pinfunction "1_1") (pintype "passive"))
    )
    (net (code "45") (name "Net-(CV_B-3)") (class "Default")
      (node (ref "CV_B") (pin "P$3") (pinfunction "3_P$3") (pintype "passive"))
      (node (ref "R31") (pin "1") (pinfunction "1_1") (pintype "passive"))
    )
    (net (code "46") (name "Net-(CV_C-3)") (class "Default")
      (node (ref "CV_C") (pin "P$3") (pinfunction "3_P$3") (pintype "passive"))
      (node (ref "R33") (pin "1") (pinfunction "1_1") (pintype "passive"))
    )
    (net (code "47") (name "Net-(CV_D-3)") (class "Default")
      (node (ref "CV_D") (pin "P$3") (pinfunction "3_P$3") (pintype "passive"))
      (node (ref "R37") (pin "1") (pinfunction "1_1") (pintype "passive"))
    )
    (net (code "48") (name "Net-(D1-C1A2)") (class "Default")
      (node (ref "D1") (pin "3") (pinfunction "C1A2_3") (pintype "passive"))
      (node (ref "R39") (pin "2") (pinfunction "2_2") (pintype "passive"))
      (node (ref "R40") (pin "1") (pinfunction "1_1") (pintype "passive"))
    )
    (net (code "49") (name "Net-(D2-C1A2)") (class "Default")
      (node (ref "D2") (pin "3") (pinfunction "C1A2_3") (pintype "passive"))
      (node (ref "R41") (pin "2") (pinfunction "2_2") (pintype "passive"))
      (node (ref "R42") (pin "1") (pinfunction "1_1") (pintype "passive"))
    )
    (net (code "50") (name "Net-(D3-C1A2)") (class "Default")
      (node (ref "D3") (pin "3") (pinfunction "C1A2_3") (pintype "passive"))
      (node (ref "R46") (pin "2") (pinfunction "2_2") (pintype "passive"))
      (node (ref "R47") (pin "1") (pinfunction "1_1") (pintype "passive"))
    )
    (net (code "51") (name "Net-(D4-C1A2)") (class "Default")
      (node (ref "D4") (pin "3") (pinfunction "C1A2_3") (pintype "passive"))
      (node (ref "R51") (pin "2") (pinfunction "2_2") (pintype "passive"))
      (node (ref "R52") (pin "1") (pinfunction "1_1") (pintype "passive"))
    )
    (net (code "52") (name "Net-(IC2A-+IN)") (class "Default")
      (node (ref "IC2") (pin "3") (pinfunction "+IN_3") (pintype "input"))
      (node (ref "R3") (pin "2") (pinfunction "2_2") (pintype "passive"))
      (node (ref "R4") (pin "1") (pinfunction "1_1") (pintype "passive"))
    )
    (net (code "53") (name "Net-(IC2A--IN)") (class "Default")
      (node (ref "IC2") (pin "2") (pinfunction "-IN_2") (pintype "input"))
      (node (ref "R1") (pin "2") (pinfunction "2_2") (pintype "passive"))
      (node (ref "R2") (pin "1") (pinfunction "1_1") (pintype "passive"))
    )
    (net (code "54") (name "Net-(IC2A-OUT)") (class "Default")
      (node (ref "IC2") (pin "1") (pinfunction "OUT_1") (pintype "output"))
      (node (ref "R1") (pin "1") (pinfunction "1_1") (pintype "passive"))
      (node (ref "R7") (pin "2") (pinfunction "2_2") (pintype "passive"))
    )
    (net (code "55") (name "Net-(IC2B-+IN)") (class "Default")
      (node (ref "IC2") (pin "5") (pinfunction "+IN_5") (pintype "input"))
      (node (ref "R5") (pin "2") (pinfunction "2_2") (pintype "passive"))
      (node (ref "R6") (pin "1") (pinfunction "1_1") (pintype "passive"))
    )
    (net (code "56") (name "Net-(IC2B--IN)") (class "Default")
      (node (ref "IC2") (pin "6") (pinfunction "-IN_6") (pintype "input"))
      (node (ref "R11") (pin "2") (pinfunction "2_2") (pintype "passive"))
      (node (ref "R12") (pin "1") (pinfunction "1_1") (pintype "passive"))
    )
    (net (code "57") (name "Net-(IC2B-OUT)") (class "Default")
      (node (ref "IC2") (pin "7") (pinfunction "OUT_7") (pintype "output"))
      (node (ref "R10") (pin "2") (pinfunction "2_2") (pintype "passive"))
      (node (ref "R11") (pin "1") (pinfunction "1_1") (pintype "passive"))
    )
    (net (code "58") (name "Net-(IC3A-+IN)") (class "Default")
      (node (ref "C21") (pin "1") (pinfunction "1_1") (pintype "passive"))
      (node (ref "IC3") (pin "3") (pinfunction "+IN_3") (pintype "input"))
      (node (ref "R18") (pin "2") (pinfunction "2_2") (pintype "passive"))
    )
    (net (code "59") (name "Net-(IC3A--IN)") (class "Default")
      (node (ref "C11") (pin "1") (pinfunction "1_1") (pintype "passive"))
      (node (ref "IC3") (pin "2") (pinfunction "-IN_2") (pintype "input"))
      (node (ref "R15") (pin "2") (pinfunction "2_2") (pintype "passive"))
    )
    (net (code "60") (name "Net-(IC3A-OUT)") (class "Default")
      (node (ref "C11") (pin "2") (pinfunction "2_2") (pintype "passive"))
      (node (ref "IC3") (pin "1") (pinfunction "OUT_1") (pintype "output"))
      (node (ref "R13") (pin "1") (pinfunction "1_1") (pintype "passive"))
      (node (ref "R14") (pin "2") (pinfunction "2_2") (pintype "passive"))
    )
    (net (code "61") (name "Net-(IC3B-+IN)") (class "Default")
      (node (ref "C22") (pin "1") (pinfunction "1_1") (pintype "passive"))
      (node (ref "IC3") (pin "5") (pinfunction "+IN_5") (pintype "input"))
      (node (ref "R20") (pin "2") (pinfunction "2_2") (pintype "passive"))
    )
    (net (code "62") (name "Net-(IC3B--IN)") (class "Default")
      (node (ref "C16") (pin "1") (pinfunction "1_1") (pintype "passive"))
      (node (ref "IC3") (pin "6") (pinfunction "-IN_6") (pintype "input"))
      (node (ref "R25") (pin "2") (pinfunction "2_2") (pintype "passive"))
    )
    (net (code "63") (name "Net-(IC3B-OUT)") (class "Default")
      (node (ref "C16") (pin "2") (pinfunction "2_2") (pintype "passive"))
      (node (ref "IC3") (pin "7") (pinfunction "OUT_7") (pintype "output"))
      (node (ref "R27") (pin "1") (pinfunction "1_1") (pintype "passive"))
      (node (ref "R28") (pin "2") (pinfunction "2_2") (pintype "passive"))
    )
    (net (code "64") (name "Net-(IC4A--IN)") (class "Default")
      (node (ref "IC4") (pin "2") (pinfunction "-IN_2") (pintype "input"))
      (node (ref "R23") (pin "1") (pinfunction "1_1") (pintype "passive"))
      (node (ref "R8") (pin "2") (pinfunction "2_2") (pintype "passive"))
      (node (ref "R9") (pin "2") (pinfunction "2_2") (pintype "passive"))
    )
    (net (code "65") (name "Net-(IC4A-OUT)") (class "Default")
      (node (ref "IC4") (pin "1") (pinfunction "OUT_1") (pintype "output"))
      (node (ref "R23") (pin "2") (pinfunction "2_2") (pintype "passive"))
      (node (ref "R40") (pin "2") (pinfunction "2_2") (pintype "passive"))
    )
    (net (code "66") (name "Net-(IC4B--IN)") (class "Default")
      (node (ref "IC4") (pin "6") (pinfunction "-IN_6") (pintype "input"))
      (node (ref "R24") (pin "1") (pinfunction "1_1") (pintype "passive"))
      (node (ref "R31") (pin "2") (pinfunction "2_2") (pintype "passive"))
      (node (ref "R32") (pin "2") (pinfunction "2_2") (pintype "passive"))
    )
    (net (code "67") (name "Net-(IC4B-OUT)") (class "Default")
      (node (ref "IC4") (pin "7") (pinfunction "OUT_7") (pintype "output"))
      (node (ref "R24") (pin "2") (pinfunction "2_2") (pintype "passive"))
      (node (ref "R42") (pin "2") (pinfunction "2_2") (pintype "passive"))
    )
    (net (code "68") (name "Net-(IC4C--IN)") (class "Default")
      (node (ref "IC4") (pin "9") (pinfunction "-IN_9") (pintype "input"))
      (node (ref "R30") (pin "2") (pinfunction "2_2") (pintype "passive"))
      (node (ref "R33") (pin "2") (pinfunction "2_2") (pintype "passive"))
      (node (ref "R35") (pin "1") (pinfunction "1_1") (pintype "passive"))
    )
    (net (code "69") (name "Net-(IC4C-OUT)") (class "Default")
      (node (ref "IC4") (pin "8") (pinfunction "OUT_8") (pintype "output"))
      (node (ref "R35") (pin "2") (pinfunction "2_2") (pintype "passive"))
      (node (ref "R47") (pin "2") (pinfunction "2_2") (pintype "passive"))
    )
    (net (code "70") (name "Net-(IC4D--IN)") (class "Default")
      (node (ref "IC4") (pin "13") (pinfunction "-IN_13") (pintype "input"))
      (node (ref "R34") (pin "1") (pinfunction "1_1") (pintype "passive"))
      (node (ref "R37") (pin "2") (pinfunction "2_2") (pintype "passive"))
      (node (ref "R38") (pin "2") (pinfunction "2_2") (pintype "passive"))
    )
    (net (code "71") (name "Net-(IC4D-OUT)") (class "Default")
      (node (ref "IC4") (pin "14") (pinfunction "OUT_14") (pintype "output"))
      (node (ref "R34") (pin "2") (pinfunction "2_2") (pintype "passive"))
      (node (ref "R52") (pin "2") (pinfunction "2_2") (pintype "passive"))
    )
    (net (code "72") (name "Net-(POT_A-Pad2)") (class "Default")
      (node (ref "POT_A") (pin "2") (pinfunction "2_2") (pintype "bidirectional"))
      (node (ref "R9") (pin "1") (pinfunction "1_1") (pintype "passive"))
    )
    (net (code "73") (name "Net-(POT_B-Pad2)") (class "Default")
      (node (ref "POT_B") (pin "2") (pinfunction "2_2") (pintype "bidirectional"))
      (node (ref "R32") (pin "1") (pinfunction "1_1") (pintype "passive"))
    )
    (net (code "74") (name "Net-(POT_C-Pad2)") (class "Default")
      (node (ref "POT_C") (pin "2") (pinfunction "2_2") (pintype "bidirectional"))
      (node (ref "R30") (pin "1") (pinfunction "1_1") (pintype "passive"))
    )
    (net (code "75") (name "Net-(POT_D-Pad2)") (class "Default")
      (node (ref "POT_D") (pin "2") (pinfunction "2_2") (pintype "bidirectional"))
      (node (ref "R38") (pin "1") (pinfunction "1_1") (pintype "passive"))
    )
    (net (code "76") (name "Net-(Q1-D)") (class "Default")
      (node (ref "JP8") (pin "10") (pinfunction "10_10") (pintype "passive"))
      (node (ref "JP8") (pin "9") (pinfunction "9_9") (pintype "passive"))
      (node (ref "Q1") (pin "3") (pinfunction "D_3") (pintype "passive"))
    )
    (net (code "77") (name "Net-(Q2-D)") (class "Default")
      (node (ref "JP8") (pin "1") (pinfunction "1_1") (pintype "passive"))
      (node (ref "JP8") (pin "2") (pinfunction "2_2") (pintype "passive"))
      (node (ref "Q2") (pin "3") (pinfunction "D_3") (pintype "passive"))
    )
    (net (code "78") (name "Net-(Q3-B)") (class "Default")
      (node (ref "Q3") (pin "1") (pinfunction "B_1") (pintype "passive"))
      (node (ref "R49") (pin "2") (pinfunction "2_2") (pintype "passive"))
      (node (ref "R50") (pin "2") (pinfunction "2_2") (pintype "passive"))
    )
    (net (code "79") (name "Net-(SW1A-CBLUE)") (class "Default")
      (node (ref "R44") (pin "1") (pinfunction "1_1") (pintype "passive"))
      (node (ref "SW1") (pin "P3") (pinfunction "CBLUE_P3") (pintype "passive"))
    )
    (net (code "80") (name "Net-(SW1A-CGREEN)") (class "Default")
      (node (ref "R45") (pin "1") (pinfunction "1_1") (pintype "passive"))
      (node (ref "SW1") (pin "P2") (pinfunction "CGREEN_P2") (pintype "passive"))
    )
    (net (code "81") (name "Net-(SW1A-CRED)") (class "Default")
      (node (ref "R43") (pin "1") (pinfunction "1_1") (pintype "passive"))
      (node (ref "SW1") (pin "P4") (pinfunction "CRED_P4") (pintype "passive"))
    )
    (net (code "82") (name "Net-(TR-3)") (class "Default")
      (node (ref "R50") (pin "1") (pinfunction "1_1") (pintype "passive"))
      (node (ref "TR") (pin "P$3") (pinfunction "3_P$3") (pintype "passive"))
    )
    (net (code "83") (name "unconnected-(OUT_L-4-PadP$2)") (class "Default")
      (node (ref "OUT_L") (pin "P$2") (pinfunction "4_P$2") (pintype "passive"))
    )
    (net (code "84") (name "unconnected-(OUT_R-4-PadP$2)") (class "Default")
      (node (ref "OUT_R") (pin "P$2") (pinfunction "4_P$2") (pintype "passive"))
    )
  )
)
